# Design1.net
KiCad netlist of a schematic drawn in EAGLE
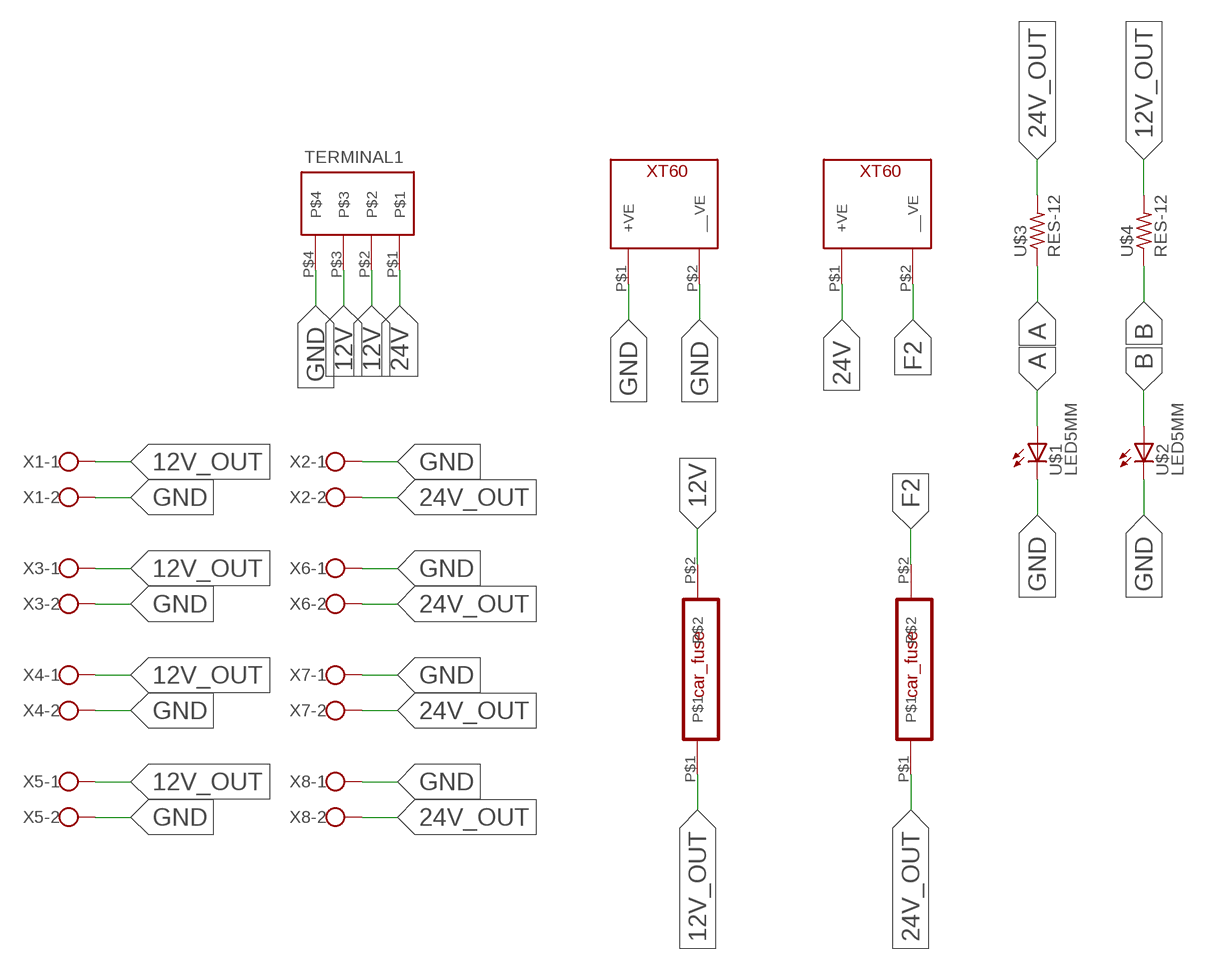
[diagram p0: schematic, sheet 1]

(export (version "E")
  (design (tool "Eeschema 10.0.6"))
  (components
    (comp (ref "FUSE_12")
      (value "CAR_FUSE")
      (footprint "eagle-import:CAR_FUSE")
      (libsource (lib "eagle-import") (part "CAR_FUSE"))
    )
    (comp (ref "FUSE_24")
      (value "CAR_FUSE")
      (footprint "eagle-import:CAR_FUSE")
      (libsource (lib "eagle-import") (part "CAR_FUSE"))
    )
    (comp (ref "SWITCH_12")
      (value "XT60_CONNECTOR")
      (footprint "eagle-import:XT60")
      (libsource (lib "eagle-import") (part "XT60_CONNECTOR"))
    )
    (comp (ref "SWITCH_24")
      (value "XT60_CONNECTOR")
      (footprint "eagle-import:XT60")
      (libsource (lib "eagle-import") (part "XT60_CONNECTOR"))
    )
    (comp (ref "TERMINAL1")
      (value "BARRIER_TERMINAL_BLOCK_4PIN_9.5MM")
      (footprint "eagle-import:BARRIER_TERMINAL_BLOCK_4PIN_9.5MM")
      (libsource (lib "eagle-import") (part "BARRIER_TERMINAL_BLOCK_4PIN_9.5MM"))
    )
    (comp (ref "U$1")
      (value "LED5MM")
      (footprint "eagle-import:LED5MM")
      (libsource (lib "eagle-import") (part "LED5MM"))
    )
    (comp (ref "U$2")
      (value "LED5MM")
      (footprint "eagle-import:LED5MM")
      (libsource (lib "eagle-import") (part "LED5MM"))
    )
    (comp (ref "U$3")
      (value "RES-12")
      (footprint "eagle-import:0207_12")
      (libsource (lib "eagle-import") (part "RES-12"))
    )
    (comp (ref "U$4")
      (value "RES-12")
      (footprint "eagle-import:0207_12")
      (libsource (lib "eagle-import") (part "RES-12"))
    )
    (comp (ref "X1")
      (value "ROSTA.POWER")
      (footprint "eagle-import:W239-302")
      (libsource (lib "eagle-import") (part "ROSTA.POWER"))
    )
    (comp (ref "X2")
      (value "ROSTA.POWER")
      (footprint "eagle-import:W239-302")
      (libsource (lib "eagle-import") (part "ROSTA.POWER"))
    )
    (comp (ref "X3")
      (value "ROSTA.POWER")
      (footprint "eagle-import:W239-302")
      (libsource (lib "eagle-import") (part "ROSTA.POWER"))
    )
    (comp (ref "X4")
      (value "ROSTA.POWER")
      (footprint "eagle-import:W239-302")
      (libsource (lib "eagle-import") (part "ROSTA.POWER"))
    )
    (comp (ref "X5")
      (value "ROSTA.POWER")
      (footprint "eagle-import:W239-302")
      (libsource (lib "eagle-import") (part "ROSTA.POWER"))
    )
    (comp (ref "X6")
      (value "ROSTA.POWER")
      (footprint "eagle-import:W239-302")
      (libsource (lib "eagle-import") (part "ROSTA.POWER"))
    )
    (comp (ref "X7")
      (value "ROSTA.POWER")
      (footprint "eagle-import:W239-302")
      (libsource (lib "eagle-import") (part "ROSTA.POWER"))
    )
    (comp (ref "X8")
      (value "ROSTA.POWER")
      (footprint "eagle-import:W239-302")
      (libsource (lib "eagle-import") (part "ROSTA.POWER"))
    )
  )
  (nets
    (net (code "1") (name "12V") (class "Default")
      (node (ref "FUSE_12") (pin "P$2") (pinfunction "P$2_P$2") (pintype "bidirectional"))
      (node (ref "TERMINAL1") (pin "P$2") (pinfunction "P$2_P$2") (pintype "bidirectional"))
      (node (ref "TERMINAL1") (pin "P$3") (pinfunction "P$3_P$3") (pintype "bidirectional"))
    )
    (net (code "2") (name "12V_OUT") (class "Default")
      (node (ref "FUSE_12") (pin "P$1") (pinfunction "P$1_P$1") (pintype "bidirectional"))
      (node (ref "U$4") (pin "2") (pinfunction "2_2") (pintype "passive"))
      (node (ref "X1") (pin "1") (pinfunction "KL_1") (pintype "passive"))
      (node (ref "X3") (pin "1") (pinfunction "KL_1") (pintype "passive"))
      (node (ref "X4") (pin "1") (pinfunction "KL_1") (pintype "passive"))
      (node (ref "X5") (pin "1") (pinfunction "KL_1") (pintype "passive"))
    )
    (net (code "3") (name "24V") (class "Default")
      (node (ref "SWITCH_24") (pin "P$1") (pinfunction "+VE_P$1") (pintype "bidirectional"))
      (node (ref "TERMINAL1") (pin "P$1") (pinfunction "P$1_P$1") (pintype "bidirectional"))
    )
    (net (code "4") (name "24V_OUT") (class "Default")
      (node (ref "FUSE_24") (pin "P$1") (pinfunction "P$1_P$1") (pintype "bidirectional"))
      (node (ref "U$3") (pin "2") (pinfunction "2_2") (pintype "passive"))
      (node (ref "X2") (pin "2") (pinfunction "KL_2") (pintype "passive"))
      (node (ref "X6") (pin "2") (pinfunction "KL_2") (pintype "passive"))
      (node (ref "X7") (pin "2") (pinfunction "KL_2") (pintype "passive"))
      (node (ref "X8") (pin "2") (pinfunction "KL_2") (pintype "passive"))
    )
    (net (code "5") (name "A") (class "Default")
      (node (ref "U$1") (pin "A") (pinfunction "A_A") (pintype "passive"))
      (node (ref "U$3") (pin "1") (pinfunction "1_1") (pintype "passive"))
    )
    (net (code "6") (name "B") (class "Default")
      (node (ref "U$2") (pin "A") (pinfunction "A_A") (pintype "passive"))
      (node (ref "U$4") (pin "1") (pinfunction "1_1") (pintype "passive"))
    )
    (net (code "7") (name "F2") (class "Default")
      (node (ref "FUSE_24") (pin "P$2") (pinfunction "P$2_P$2") (pintype "bidirectional"))
      (node (ref "SWITCH_24") (pin "P$2") (pinfunction "__VE_P$2") (pintype "bidirectional"))
    )
    (net (code "8") (name "GND") (class "Default")
      (node (ref "SWITCH_12") (pin "P$1") (pinfunction "+VE_P$1") (pintype "bidirectional"))
      (node (ref "SWITCH_12") (pin "P$2") (pinfunction "__VE_P$2") (pintype "bidirectional"))
      (node (ref "TERMINAL1") (pin "P$4") (pinfunction "P$4_P$4") (pintype "bidirectional"))
      (node (ref "U$1") (pin "K") (pinfunction "C_K") (pintype "passive"))
      (node (ref "U$2") (pin "K") (pinfunction "C_K") (pintype "passive"))
      (node (ref "X1") (pin "2") (pinfunction "KL_2") (pintype "passive"))
      (node (ref "X2") (pin "1") (pinfunction "KL_1") (pintype "passive"))
      (node (ref "X3") (pin "2") (pinfunction "KL_2") (pintype "passive"))
      (node (ref "X4") (pin "2") (pinfunction "KL_2") (pintype "passive"))
      (node (ref "X5") (pin "2") (pinfunction "KL_2") (pintype "passive"))
      (node (ref "X6") (pin "1") (pinfunction "KL_1") (pintype "passive"))
      (node (ref "X7") (pin "1") (pinfunction "KL_1") (pintype "passive"))
      (node (ref "X8") (pin "1") (pinfunction "KL_1") (pintype "passive"))
    )
  )
)
